# Board_V05.net
KiCad netlist of a schematic drawn in EAGLE
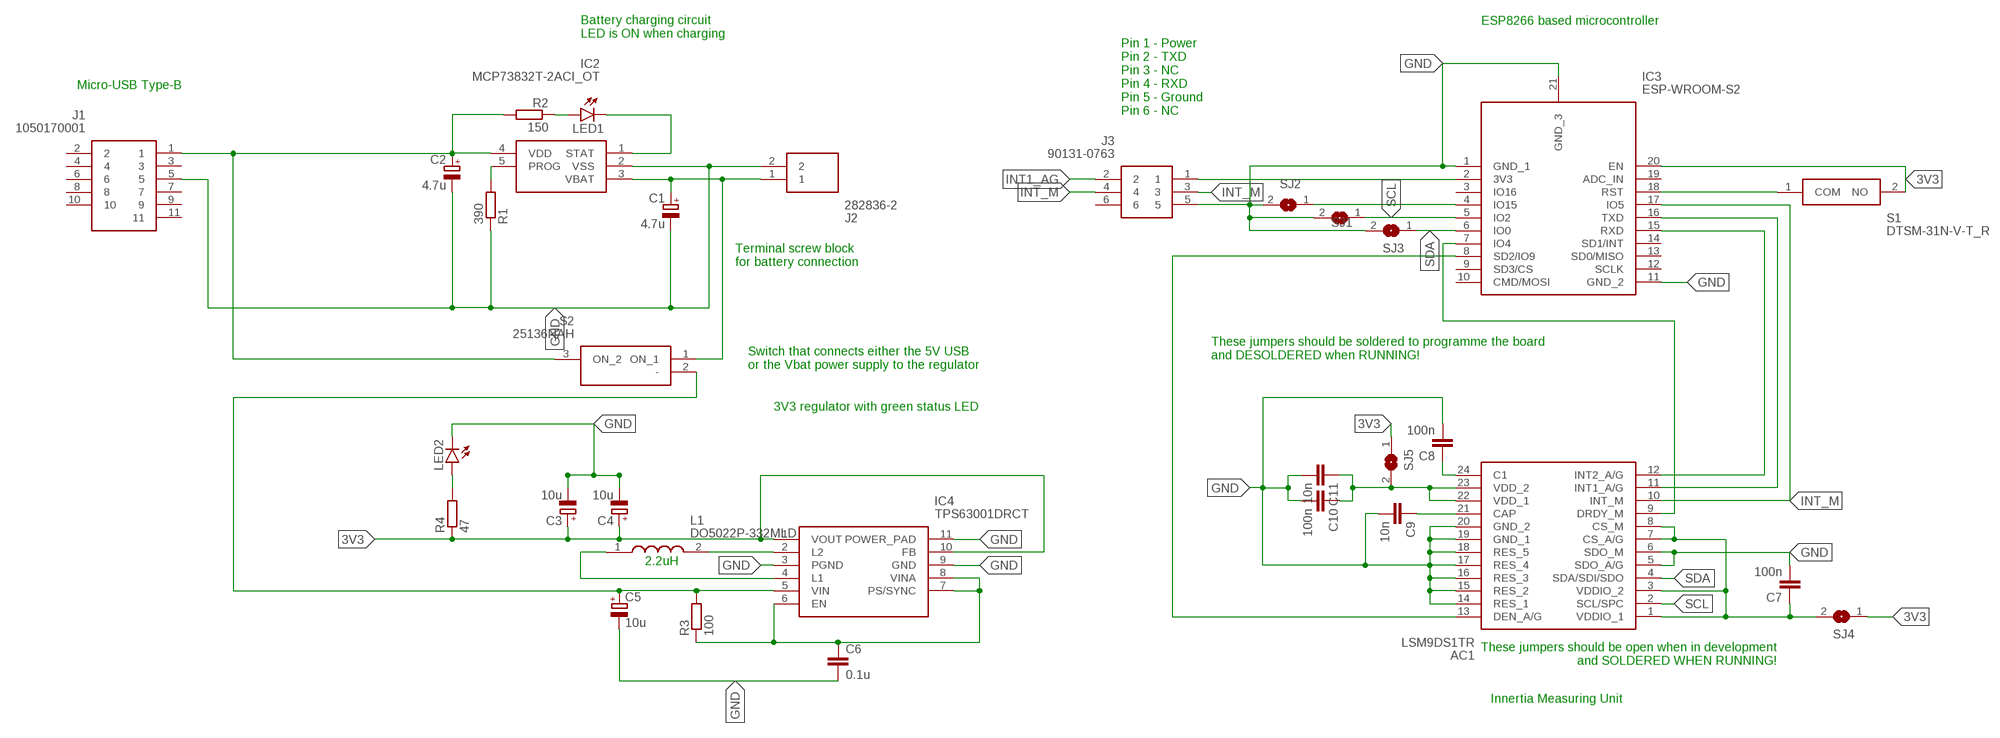
[diagram p0: schematic, sheet 1]

(export (version "E")
  (design (tool "Eeschema 10.0.6"))
  (components
    (comp (ref "AC1")
      (value "LSM9DS1TR")
      (footprint "eagle-import:LGA-24L(3X3.5X1MM)")
      (fields (field (name "MOUSER_PART_NUMBER") "511-LSM9DS1TR") (field (name "RS_PART_NUMBER") "1660908"))
      (libsource (lib "eagle-import") (part "LSM9DS1TR"))
    )
    (comp (ref "C1")
      (value "4.7u")
      (footprint "eagle-import:D_7343-31R")
      (libsource (lib "eagle-import") (part "CPOL-EUD/7343-31R"))
    )
    (comp (ref "C2")
      (value "4.7u")
      (footprint "eagle-import:D_7343-31R")
      (libsource (lib "eagle-import") (part "CPOL-EUD/7343-31R"))
    )
    (comp (ref "C3")
      (value "10u")
      (footprint "eagle-import:D_7343-31R")
      (libsource (lib "eagle-import") (part "CPOL-EUD/7343-31R"))
    )
    (comp (ref "C4")
      (value "10u")
      (footprint "eagle-import:D_7343-31R")
      (libsource (lib "eagle-import") (part "CPOL-EUD/7343-31R"))
    )
    (comp (ref "C5")
      (value "10u")
      (footprint "eagle-import:D_7343-31R")
      (libsource (lib "eagle-import") (part "CPOL-EUD/7343-31R"))
    )
    (comp (ref "C6")
      (value "0.1u")
      (footprint "eagle-import:C0402")
      (libsource (lib "eagle-import") (part "C-EUC0402"))
    )
    (comp (ref "C7")
      (value "100n")
      (footprint "eagle-import:C0805")
      (libsource (lib "eagle-import") (part "C-EUC0805"))
    )
    (comp (ref "C8")
      (value "100n")
      (footprint "eagle-import:C0805")
      (libsource (lib "eagle-import") (part "C-EUC0805"))
    )
    (comp (ref "C9")
      (value "10n")
      (footprint "eagle-import:C0805")
      (libsource (lib "eagle-import") (part "C-EUC0805"))
    )
    (comp (ref "C10")
      (value "100n")
      (footprint "eagle-import:C0805")
      (libsource (lib "eagle-import") (part "C-EUC0805"))
    )
    (comp (ref "C11")
      (value "10n")
      (footprint "eagle-import:C0805")
      (libsource (lib "eagle-import") (part "C-EUC0805"))
    )
    (comp (ref "IC2")
      (value "MCP73832T-2ACI_OT")
      (footprint "eagle-import:SOT95P270X145-5N")
      (fields
        (field (name "MANUFACTURER_PART_NUMBER") "MCP73832T-2ACI/OT")
        (field (name "MOUSER_PART_NUMBER") "579-MCP73832T-2ACIOT")
        (field (name "RS_PART_NUMBER") "9122897")
      )
      (libsource (lib "eagle-import") (part "MCP73832T-2ACI_OT"))
    )
    (comp (ref "IC3")
      (value "ESP-WROOM-S2")
      (footprint "eagle-import:QFN150P1600X1700X315-21N")
      (libsource (lib "eagle-import") (part "ESP-WROOM-S2"))
    )
    (comp (ref "IC4")
      (value "TPS63001DRCT")
      (footprint "eagle-import:SON50P300X300X100-11N")
      (fields (field (name "RS_PART_NUMBER") "7968405"))
      (libsource (lib "eagle-import") (part "TPS63001DRCT"))
    )
    (comp (ref "J1")
      (value "1050170001")
      (footprint "eagle-import:MICROUSB-BTYPE")
      (libsource (lib "eagle-import") (part "1050170001"))
    )
    (comp (ref "J2")
      (value "282836-2")
      (footprint "eagle-import:SHDR2W100P0X500_1X2_1000X820X1")
      (fields (field (name "MOUSER_PART_NUMBER") "571-2828362") (field (name "RS_PART_NUMBER") "1354983"))
      (libsource (lib "eagle-import") (part "282836-2"))
    )
    (comp (ref "J3")
      (value "90131-0763")
      (footprint "eagle-import:HDRV6W90P254_2X3_762X500X560P")
      (fields (field (name "MOUSER_PART_NUMBER") "538-90131-0763") (field (name "RS_PART_NUMBER") "3606443P"))
      (libsource (lib "eagle-import") (part "90131-0763"))
    )
    (comp (ref "L1")
      (value "DO5022P-332MLD")
      (footprint "eagle-import:DO5022P-104MLD")
      (fields (field (name "MOUSER_PART_NUMBER") "994-DO5022P-332MLD"))
      (libsource (lib "eagle-import") (part "DO5022P-332MLD"))
    )
    (comp (ref "LED1")
      (value "LED5MM")
      (footprint "eagle-import:LED5MM")
      (libsource (lib "eagle-import") (part "LED5MM"))
    )
    (comp (ref "LED2")
      (value "LED5MM")
      (footprint "eagle-import:LED5MM")
      (libsource (lib "eagle-import") (part "LED5MM"))
    )
    (comp (ref "R1")
      (value "390")
      (footprint "eagle-import:R0805")
      (libsource (lib "eagle-import") (part "R-EU_R0805"))
    )
    (comp (ref "R2")
      (value "150")
      (footprint "eagle-import:R0805")
      (libsource (lib "eagle-import") (part "R-EU_R0805"))
    )
    (comp (ref "R3")
      (value "100")
      (footprint "eagle-import:R0805")
      (libsource (lib "eagle-import") (part "R-EU_R0805"))
    )
    (comp (ref "R4")
      (value "47")
      (footprint "eagle-import:R0805")
      (libsource (lib "eagle-import") (part "R-EU_R0805"))
    )
    (comp (ref "S1")
      (value "DTSM-31N-V-T_R")
      (footprint "eagle-import:DTSM32NVTR")
      (fields
        (field (name "MANUFACTURER_PART_NUMBER") "DTSM-31N-V-T/R")
        (field (name "MOUSER_PART_NUMBER") "113-DTSM31NVTR")
      )
      (libsource (lib "eagle-import") (part "DTSM-31N-V-T_R"))
    )
    (comp (ref "S2")
      (value "25136NAH")
      (footprint "eagle-import:25136NAH")
      (fields (field (name "MOUSER_PART_NUMBER") "642-25136NAH") (field (name "RS_PART_NUMBER") "0339673A"))
      (libsource (lib "eagle-import") (part "25136NAH"))
    )
    (comp (ref "SJ1")
      (value "SJW")
      (footprint "eagle-import:SJW")
      (libsource (lib "eagle-import") (part "SJW"))
    )
    (comp (ref "SJ2")
      (value "SJW")
      (footprint "eagle-import:SJW")
      (libsource (lib "eagle-import") (part "SJW"))
    )
    (comp (ref "SJ3")
      (value "SJW")
      (footprint "eagle-import:SJW")
      (libsource (lib "eagle-import") (part "SJW"))
    )
    (comp (ref "SJ4")
      (value "SJW")
      (footprint "eagle-import:SJW")
      (libsource (lib "eagle-import") (part "SJW"))
    )
    (comp (ref "SJ5")
      (value "SJW")
      (footprint "eagle-import:SJW")
      (libsource (lib "eagle-import") (part "SJW"))
    )
  )
  (nets
    (net (code "1") (name "3V3") (class "Default")
      (node (ref "C3") (pin "+") (pinfunction "+_+") (pintype "passive"))
      (node (ref "C4") (pin "+") (pinfunction "+_+") (pintype "passive"))
      (node (ref "IC3") (pin "2") (pinfunction "3V3_2") (pintype "power_in"))
      (node (ref "IC3") (pin "20") (pinfunction "EN_20") (pintype "bidirectional"))
      (node (ref "IC4") (pin "1") (pinfunction "VOUT_1") (pintype "bidirectional"))
      (node (ref "IC4") (pin "10") (pinfunction "FB_10") (pintype "bidirectional"))
      (node (ref "J3") (pin "1") (pinfunction "1_1") (pintype "bidirectional"))
      (node (ref "R4") (pin "1") (pinfunction "1_1") (pintype "passive"))
      (node (ref "S1") (pin "2") (pinfunction "NO_2") (pintype "bidirectional"))
      (node (ref "SJ4") (pin "1") (pinfunction "1_1") (pintype "passive"))
      (node (ref "SJ5") (pin "1") (pinfunction "1_1") (pintype "passive"))
    )
    (net (code "2") (name "GND") (class "Default")
      (node (ref "AC1") (pin "14") (pinfunction "RES_1_14") (pintype "power_in"))
      (node (ref "AC1") (pin "15") (pinfunction "RES_2_15") (pintype "power_in"))
      (node (ref "AC1") (pin "16") (pinfunction "RES_3_16") (pintype "power_in"))
      (node (ref "AC1") (pin "17") (pinfunction "RES_4_17") (pintype "power_in"))
      (node (ref "AC1") (pin "18") (pinfunction "RES_5_18") (pintype "power_in"))
      (node (ref "AC1") (pin "19") (pinfunction "GND_1_19") (pintype "power_in"))
      (node (ref "AC1") (pin "20") (pinfunction "GND_2_20") (pintype "power_in"))
      (node (ref "AC1") (pin "5") (pinfunction "SDO_A/G_5") (pintype "output"))
      (node (ref "AC1") (pin "6") (pinfunction "SDO_M_6") (pintype "output"))
      (node (ref "C1") (pin "-") (pinfunction "-_-") (pintype "passive"))
      (node (ref "C10") (pin "2") (pinfunction "2_2") (pintype "passive"))
      (node (ref "C11") (pin "2") (pinfunction "2_2") (pintype "passive"))
      (node (ref "C2") (pin "-") (pinfunction "-_-") (pintype "passive"))
      (node (ref "C3") (pin "-") (pinfunction "-_-") (pintype "passive"))
      (node (ref "C4") (pin "-") (pinfunction "-_-") (pintype "passive"))
      (node (ref "C5") (pin "-") (pinfunction "-_-") (pintype "passive"))
      (node (ref "C6") (pin "2") (pinfunction "2_2") (pintype "passive"))
      (node (ref "C7") (pin "2") (pinfunction "2_2") (pintype "passive"))
      (node (ref "C8") (pin "2") (pinfunction "2_2") (pintype "passive"))
      (node (ref "C9") (pin "2") (pinfunction "2_2") (pintype "passive"))
      (node (ref "IC2") (pin "2") (pinfunction "VSS_2") (pintype "power_in"))
      (node (ref "IC3") (pin "1") (pinfunction "GND_1_1") (pintype "power_in"))
      (node (ref "IC3") (pin "11") (pinfunction "GND_2_11") (pintype "power_in"))
      (node (ref "IC3") (pin "21") (pinfunction "GND_3_21") (pintype "power_in"))
      (node (ref "IC4") (pin "11") (pinfunction "POWER_PAD_11") (pintype "bidirectional"))
      (node (ref "IC4") (pin "3") (pinfunction "PGND_3") (pintype "bidirectional"))
      (node (ref "IC4") (pin "9") (pinfunction "GND_9") (pintype "bidirectional"))
      (node (ref "J1") (pin "5") (pinfunction "5_5") (pintype "bidirectional"))
      (node (ref "J2") (pin "2") (pinfunction "2_2") (pintype "bidirectional"))
      (node (ref "J3") (pin "5") (pinfunction "5_5") (pintype "bidirectional"))
      (node (ref "LED2") (pin "K") (pinfunction "C_K") (pintype "passive"))
      (node (ref "R1") (pin "1") (pinfunction "1_1") (pintype "passive"))
      (node (ref "SJ1") (pin "2") (pinfunction "2_2") (pintype "passive"))
      (node (ref "SJ2") (pin "2") (pinfunction "2_2") (pintype "passive"))
      (node (ref "SJ3") (pin "2") (pinfunction "2_2") (pintype "passive"))
    )
    (net (code "3") (name "INT1_AG") (class "Default")
      (node (ref "AC1") (pin "11") (pinfunction "INT1_A/G_11") (pintype "bidirectional"))
      (node (ref "IC3") (pin "16") (pinfunction "TXD_16") (pintype "bidirectional"))
      (node (ref "J3") (pin "2") (pinfunction "2_2") (pintype "bidirectional"))
    )
    (net (code "4") (name "INT_M") (class "Default")
      (node (ref "AC1") (pin "10") (pinfunction "INT_M_10") (pintype "bidirectional"))
      (node (ref "IC3") (pin "17") (pinfunction "IO5_17") (pintype "bidirectional"))
      (node (ref "J3") (pin "3") (pinfunction "3_3") (pintype "bidirectional"))
      (node (ref "J3") (pin "4") (pinfunction "4_4") (pintype "bidirectional"))
    )
    (net (code "5") (name "Net-(AC1-C1)") (class "Default")
      (node (ref "AC1") (pin "24") (pinfunction "C1_24") (pintype "bidirectional"))
      (node (ref "C8") (pin "1") (pinfunction "1_1") (pintype "passive"))
    )
    (net (code "6") (name "Net-(AC1-CAP)") (class "Default")
      (node (ref "AC1") (pin "21") (pinfunction "CAP_21") (pintype "power_in"))
      (node (ref "C9") (pin "1") (pinfunction "1_1") (pintype "passive"))
    )
    (net (code "7") (name "Net-(AC1-CS_A{slash}G)") (class "Default")
      (node (ref "AC1") (pin "1") (pinfunction "VDDIO_1_1") (pintype "power_in"))
      (node (ref "AC1") (pin "3") (pinfunction "VDDIO_2_3") (pintype "power_in"))
      (node (ref "AC1") (pin "7") (pinfunction "CS_A/G_7") (pintype "bidirectional"))
      (node (ref "AC1") (pin "8") (pinfunction "CS_M_8") (pintype "bidirectional"))
      (node (ref "C7") (pin "1") (pinfunction "1_1") (pintype "passive"))
      (node (ref "SJ4") (pin "2") (pinfunction "2_2") (pintype "passive"))
    )
    (net (code "8") (name "Net-(AC1-DEN_A{slash}G)") (class "Default")
      (node (ref "AC1") (pin "13") (pinfunction "DEN_A/G_13") (pintype "bidirectional"))
      (node (ref "IC3") (pin "8") (pinfunction "SD2/IO9_8") (pintype "bidirectional"))
    )
    (net (code "9") (name "Net-(AC1-DRDY_M)") (class "Default")
      (node (ref "AC1") (pin "9") (pinfunction "DRDY_M_9") (pintype "bidirectional"))
      (node (ref "IC3") (pin "7") (pinfunction "IO4_7") (pintype "bidirectional"))
    )
    (net (code "10") (name "Net-(AC1-INT2_A{slash}G)") (class "Default")
      (node (ref "AC1") (pin "12") (pinfunction "INT2_A/G_12") (pintype "bidirectional"))
      (node (ref "IC3") (pin "15") (pinfunction "RXD_15") (pintype "bidirectional"))
    )
    (net (code "11") (name "Net-(AC1-VDD_1)") (class "Default")
      (node (ref "AC1") (pin "22") (pinfunction "VDD_1_22") (pintype "power_in"))
      (node (ref "AC1") (pin "23") (pinfunction "VDD_2_23") (pintype "power_in"))
      (node (ref "C10") (pin "1") (pinfunction "1_1") (pintype "passive"))
      (node (ref "C11") (pin "1") (pinfunction "1_1") (pintype "passive"))
      (node (ref "SJ5") (pin "2") (pinfunction "2_2") (pintype "passive"))
    )
    (net (code "12") (name "Net-(IC2-PROG)") (class "Default")
      (node (ref "IC2") (pin "5") (pinfunction "PROG_5") (pintype "bidirectional"))
      (node (ref "R1") (pin "2") (pinfunction "2_2") (pintype "passive"))
    )
    (net (code "13") (name "Net-(IC2-STAT)") (class "Default")
      (node (ref "IC2") (pin "1") (pinfunction "STAT_1") (pintype "bidirectional"))
      (node (ref "LED1") (pin "K") (pinfunction "C_K") (pintype "passive"))
    )
    (net (code "14") (name "Net-(IC2-VBAT)") (class "Default")
      (node (ref "C1") (pin "+") (pinfunction "+_+") (pintype "passive"))
      (node (ref "IC2") (pin "3") (pinfunction "VBAT_3") (pintype "bidirectional"))
      (node (ref "J2") (pin "1") (pinfunction "1_1") (pintype "bidirectional"))
      (node (ref "S2") (pin "1") (pinfunction "ON_1_1") (pintype "bidirectional"))
    )
    (net (code "15") (name "Net-(IC2-VDD)") (class "Default")
      (node (ref "C2") (pin "+") (pinfunction "+_+") (pintype "passive"))
      (node (ref "IC2") (pin "4") (pinfunction "VDD_4") (pintype "power_in"))
      (node (ref "J1") (pin "1") (pinfunction "1_1") (pintype "bidirectional"))
      (node (ref "R2") (pin "2") (pinfunction "2_2") (pintype "passive"))
      (node (ref "S2") (pin "3") (pinfunction "ON_2_3") (pintype "bidirectional"))
    )
    (net (code "16") (name "Net-(IC3-IO15)") (class "Default")
      (node (ref "IC3") (pin "4") (pinfunction "IO15_4") (pintype "bidirectional"))
      (node (ref "SJ2") (pin "1") (pinfunction "1_1") (pintype "passive"))
    )
    (net (code "17") (name "Net-(IC3-RST)") (class "Default")
      (node (ref "IC3") (pin "18") (pinfunction "RST_18") (pintype "input"))
      (node (ref "S1") (pin "1") (pinfunction "COM_1") (pintype "bidirectional"))
    )
    (net (code "18") (name "Net-(IC4-EN)") (class "Default")
      (node (ref "C6") (pin "1") (pinfunction "1_1") (pintype "passive"))
      (node (ref "IC4") (pin "6") (pinfunction "EN_6") (pintype "bidirectional"))
      (node (ref "IC4") (pin "7") (pinfunction "PS/SYNC_7") (pintype "bidirectional"))
      (node (ref "IC4") (pin "8") (pinfunction "VINA_8") (pintype "bidirectional"))
      (node (ref "R3") (pin "1") (pinfunction "1_1") (pintype "passive"))
    )
    (net (code "19") (name "Net-(IC4-L1)") (class "Default")
      (node (ref "IC4") (pin "4") (pinfunction "L1_4") (pintype "bidirectional"))
      (node (ref "L1") (pin "1") (pinfunction "1_1") (pintype "bidirectional"))
    )
    (net (code "20") (name "Net-(IC4-L2)") (class "Default")
      (node (ref "IC4") (pin "2") (pinfunction "L2_2") (pintype "bidirectional"))
      (node (ref "L1") (pin "2") (pinfunction "2_2") (pintype "bidirectional"))
    )
    (net (code "21") (name "Net-(IC4-VIN)") (class "Default")
      (node (ref "C5") (pin "+") (pinfunction "+_+") (pintype "passive"))
      (node (ref "IC4") (pin "5") (pinfunction "VIN_5") (pintype "bidirectional"))
      (node (ref "R3") (pin "2") (pinfunction "2_2") (pintype "passive"))
      (node (ref "S2") (pin "2") (pinfunction "-_2") (pintype "bidirectional"))
    )
    (net (code "22") (name "Net-(LED1-PadA)") (class "Default")
      (node (ref "LED1") (pin "A") (pinfunction "A_A") (pintype "passive"))
      (node (ref "R2") (pin "1") (pinfunction "1_1") (pintype "passive"))
    )
    (net (code "23") (name "Net-(LED2-PadA)") (class "Default")
      (node (ref "LED2") (pin "A") (pinfunction "A_A") (pintype "passive"))
      (node (ref "R4") (pin "2") (pinfunction "2_2") (pintype "passive"))
    )
    (net (code "24") (name "SCL") (class "Default")
      (node (ref "AC1") (pin "2") (pinfunction "SCL/SPC_2") (pintype "output"))
      (node (ref "IC3") (pin "5") (pinfunction "IO2_5") (pintype "bidirectional"))
      (node (ref "SJ1") (pin "1") (pinfunction "1_1") (pintype "passive"))
    )
    (net (code "25") (name "SDA") (class "Default")
      (node (ref "AC1") (pin "4") (pinfunction "SDA/SDI/SDO_4") (pintype "bidirectional"))
      (node (ref "IC3") (pin "6") (pinfunction "IO0_6") (pintype "bidirectional"))
      (node (ref "SJ3") (pin "1") (pinfunction "1_1") (pintype "passive"))
    )
    (net (code "26") (name "unconnected-(IC3-ADC_IN-Pad19)") (class "Default")
      (node (ref "IC3") (pin "19") (pinfunction "ADC_IN_19") (pintype "input"))
    )
    (net (code "27") (name "unconnected-(IC3-CMD{slash}MOSI-Pad10)") (class "Default")
      (node (ref "IC3") (pin "10") (pinfunction "CMD/MOSI_10") (pintype "bidirectional"))
    )
    (net (code "28") (name "unconnected-(IC3-IO16-Pad3)") (class "Default")
      (node (ref "IC3") (pin "3") (pinfunction "IO16_3") (pintype "bidirectional"))
    )
    (net (code "29") (name "unconnected-(IC3-SCLK-Pad12)") (class "Default")
      (node (ref "IC3") (pin "12") (pinfunction "SCLK_12") (pintype "bidirectional"))
    )
    (net (code "30") (name "unconnected-(IC3-SD0{slash}MISO-Pad13)") (class "Default")
      (node (ref "IC3") (pin "13") (pinfunction "SD0/MISO_13") (pintype "bidirectional"))
    )
    (net (code "31") (name "unconnected-(IC3-SD1{slash}INT-Pad14)") (class "Default")
      (node (ref "IC3") (pin "14") (pinfunction "SD1/INT_14") (pintype "bidirectional"))
    )
    (net (code "32") (name "unconnected-(IC3-SD3{slash}CS-Pad9)") (class "Default")
      (node (ref "IC3") (pin "9") (pinfunction "SD3/CS_9") (pintype "bidirectional"))
    )
    (net (code "33") (name "unconnected-(J1-Pad2)") (class "Default")
      (node (ref "J1") (pin "2") (pinfunction "2_2") (pintype "bidirectional"))
    )
    (net (code "34") (name "unconnected-(J1-Pad3)") (class "Default")
      (node (ref "J1") (pin "3") (pinfunction "3_3") (pintype "bidirectional"))
    )
    (net (code "35") (name "unconnected-(J1-Pad4)") (class "Default")
      (node (ref "J1") (pin "4") (pinfunction "4_4") (pintype "bidirectional"))
    )
    (net (code "36") (name "unconnected-(J1-Pad6)") (class "Default")
      (node (ref "J1") (pin "6") (pinfunction "6_6") (pintype "bidirectional"))
    )
    (net (code "37") (name "unconnected-(J1-Pad7)") (class "Default")
      (node (ref "J1") (pin "7") (pinfunction "7_7") (pintype "bidirectional"))
    )
    (net (code "38") (name "unconnected-(J1-Pad8)") (class "Default")
      (node (ref "J1") (pin "8") (pinfunction "8_8") (pintype "bidirectional"))
    )
    (net (code "39") (name "unconnected-(J1-Pad9)") (class "Default")
      (node (ref "J1") (pin "9") (pinfunction "9_9") (pintype "bidirectional"))
    )
    (net (code "40") (name "unconnected-(J1-Pad10)") (class "Default")
      (node (ref "J1") (pin "10") (pinfunction "10_10") (pintype "bidirectional"))
    )
    (net (code "41") (name "unconnected-(J1-Pad11)") (class "Default")
      (node (ref "J1") (pin "11") (pinfunction "11_11") (pintype "bidirectional"))
    )
    (net (code "42") (name "unconnected-(J3-Pad6)") (class "Default")
      (node (ref "J3") (pin "6") (pinfunction "6_6") (pintype "bidirectional"))
    )
  )
)
